# Lesson_06.net
KiCad netlist of a schematic drawn in Altium Designer
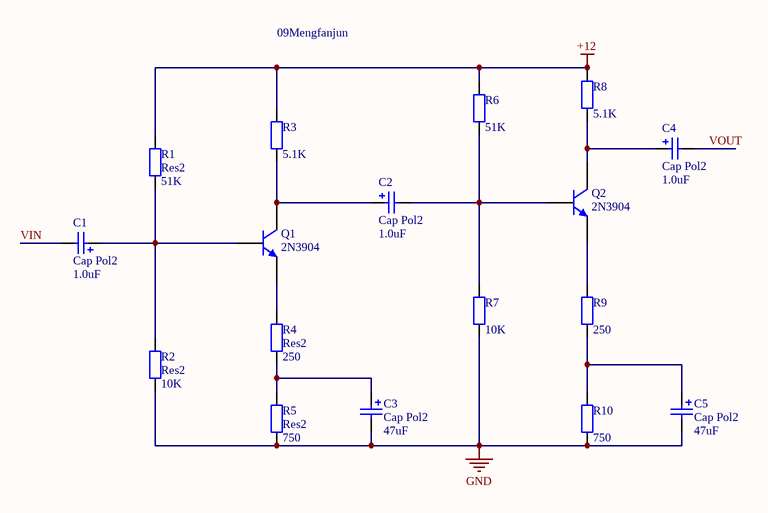
[diagram p0: Lesson_06.SchDoc]

(export (version "E")
  (design (tool "Eeschema 10.0.6"))
  (components
    (comp (ref "C1")
      (value "Cap Pol2")
      (footprint "POLAR0.8")
      (description "Polarized Capacitor (Axial)")
      (fields (field (name "ALTIUM_VALUE") "1.0uF") (field (name "PUBLISHER") "Altium Limited"))
      (libsource (lib "Miscellaneous Devices") (part "Cap Pol2"))
    )
    (comp (ref "C2")
      (value "Cap Pol2")
      (footprint "POLAR0.8")
      (description "Polarized Capacitor (Axial)")
      (fields (field (name "ALTIUM_VALUE") "1.0uF") (field (name "PUBLISHER") "Altium Limited"))
      (libsource (lib "Miscellaneous Devices") (part "Cap Pol2"))
    )
    (comp (ref "C3")
      (value "Cap Pol2")
      (footprint "POLAR0.8")
      (description "Polarized Capacitor (Axial)")
      (fields (field (name "ALTIUM_VALUE") "47uF") (field (name "PUBLISHER") "Altium Limited"))
      (libsource (lib "Miscellaneous Devices") (part "Cap Pol2"))
    )
    (comp (ref "C4")
      (value "Cap Pol2")
      (footprint "POLAR0.8")
      (description "Polarized Capacitor (Axial)")
      (fields (field (name "ALTIUM_VALUE") "1.0uF") (field (name "PUBLISHER") "Altium Limited"))
      (libsource (lib "Miscellaneous Devices") (part "Cap Pol2"))
    )
    (comp (ref "C5")
      (value "Cap Pol2")
      (footprint "POLAR0.8")
      (description "Polarized Capacitor (Axial)")
      (fields (field (name "ALTIUM_VALUE") "47uF") (field (name "PUBLISHER") "Altium Limited"))
      (libsource (lib "Miscellaneous Devices") (part "Cap Pol2"))
    )
    (comp (ref "Q1")
      (value "2N3904")
      (footprint "TO-92A")
      (description "NPN General Purpose Amplifier")
      (fields (field (name "PUBLISHER") "Altium Limited"))
      (libsource (lib "Miscellaneous Devices") (part "2N3904"))
    )
    (comp (ref "Q2")
      (value "2N3904")
      (footprint "TO-92A")
      (description "NPN General Purpose Amplifier")
      (fields (field (name "PUBLISHER") "Altium Limited"))
      (libsource (lib "Miscellaneous Devices") (part "2N3904"))
    )
    (comp (ref "R1")
      (value "Res2")
      (footprint "AXIAL-0.4")
      (description "Resistor")
      (fields (field (name "ALTIUM_VALUE") "51K") (field (name "PUBLISHER") "Altium Limited"))
      (libsource (lib "Miscellaneous Devices") (part "Res2"))
    )
    (comp (ref "R2")
      (value "Res2")
      (footprint "AXIAL-0.4")
      (description "Resistor")
      (fields (field (name "ALTIUM_VALUE") "10K") (field (name "PUBLISHER") "Altium Limited"))
      (libsource (lib "Miscellaneous Devices") (part "Res2"))
    )
    (comp (ref "R3")
      (value "5.1K")
      (footprint "AXIAL-0.4")
      (description "Resistor")
      (fields (field (name "Comment") "Res2") (field (name "PUBLISHER") "Altium Limited"))
      (libsource (lib "Miscellaneous Devices") (part "Res2"))
    )
    (comp (ref "R4")
      (value "Res2")
      (footprint "AXIAL-0.4")
      (description "Resistor")
      (fields (field (name "ALTIUM_VALUE") "250") (field (name "PUBLISHER") "Altium Limited"))
      (libsource (lib "Miscellaneous Devices") (part "Res2"))
    )
    (comp (ref "R5")
      (value "Res2")
      (footprint "AXIAL-0.4")
      (description "Resistor")
      (fields (field (name "ALTIUM_VALUE") "750") (field (name "PUBLISHER") "Altium Limited"))
      (libsource (lib "Miscellaneous Devices") (part "Res2"))
    )
    (comp (ref "R6")
      (value "51K")
      (footprint "AXIAL-0.4")
      (description "Resistor")
      (fields (field (name "Comment") "Res2") (field (name "PUBLISHER") "Altium Limited"))
      (libsource (lib "Miscellaneous Devices") (part "Res2"))
    )
    (comp (ref "R7")
      (value "10K")
      (footprint "AXIAL-0.4")
      (description "Resistor")
      (fields (field (name "PUBLISHER") "Altium Limited"))
      (libsource (lib "Miscellaneous Devices") (part "Res2"))
    )
    (comp (ref "R8")
      (value "5.1K")
      (footprint "AXIAL-0.4")
      (description "Resistor")
      (fields (field (name "Comment") "Res2") (field (name "PUBLISHER") "Altium Limited"))
      (libsource (lib "Miscellaneous Devices") (part "Res2"))
    )
    (comp (ref "R9")
      (value "250")
      (footprint "AXIAL-0.4")
      (description "Resistor")
      (fields (field (name "Comment") "Res2") (field (name "PUBLISHER") "Altium Limited"))
      (libsource (lib "Miscellaneous Devices") (part "Res2"))
    )
    (comp (ref "R10")
      (value "750")
      (footprint "AXIAL-0.4")
      (description "Resistor")
      (fields (field (name "Comment") "Res2") (field (name "PUBLISHER") "Altium Limited"))
      (libsource (lib "Miscellaneous Devices") (part "Res2"))
    )
  )
  (nets
    (net (code "1") (name "+12") (class "Default")
      (node (ref "R1") (pin "2") (pinfunction "2_2") (pintype "passive"))
      (node (ref "R3") (pin "2") (pinfunction "2_2") (pintype "passive"))
      (node (ref "R6") (pin "2") (pinfunction "2_2") (pintype "passive"))
      (node (ref "R8") (pin "2") (pinfunction "2_2") (pintype "passive"))
    )
    (net (code "2") (name "/VIN") (class "Default")
      (node (ref "C1") (pin "2") (pinfunction "2_2") (pintype "passive"))
    )
    (net (code "3") (name "/VOUT") (class "Default")
      (node (ref "C4") (pin "2") (pinfunction "2_2") (pintype "passive"))
    )
    (net (code "4") (name "GND") (class "Default")
      (node (ref "C3") (pin "2") (pinfunction "2_2") (pintype "passive"))
      (node (ref "C5") (pin "2") (pinfunction "2_2") (pintype "passive"))
      (node (ref "R10") (pin "1") (pinfunction "1_1") (pintype "passive"))
      (node (ref "R2") (pin "1") (pinfunction "1_1") (pintype "passive"))
      (node (ref "R5") (pin "1") (pinfunction "1_1") (pintype "passive"))
      (node (ref "R7") (pin "1") (pinfunction "1_1") (pintype "passive"))
    )
    (net (code "5") (name "Net-(C3-Pad1)") (class "Default")
      (node (ref "C3") (pin "1") (pinfunction "1_1") (pintype "passive"))
      (node (ref "R4") (pin "1") (pinfunction "1_1") (pintype "passive"))
      (node (ref "R5") (pin "2") (pinfunction "2_2") (pintype "passive"))
    )
    (net (code "6") (name "Net-(C5-Pad1)") (class "Default")
      (node (ref "C5") (pin "1") (pinfunction "1_1") (pintype "passive"))
      (node (ref "R10") (pin "2") (pinfunction "2_2") (pintype "passive"))
      (node (ref "R9") (pin "1") (pinfunction "1_1") (pintype "passive"))
    )
    (net (code "7") (name "Net-(Q1-B)") (class "Default")
      (node (ref "C1") (pin "1") (pinfunction "1_1") (pintype "passive"))
      (node (ref "Q1") (pin "2") (pinfunction "B_2") (pintype "passive"))
      (node (ref "R1") (pin "1") (pinfunction "1_1") (pintype "passive"))
      (node (ref "R2") (pin "2") (pinfunction "2_2") (pintype "passive"))
    )
    (net (code "8") (name "Net-(Q1-C)") (class "Default")
      (node (ref "C2") (pin "1") (pinfunction "1_1") (pintype "passive"))
      (node (ref "Q1") (pin "3") (pinfunction "C_3") (pintype "passive"))
      (node (ref "R3") (pin "1") (pinfunction "1_1") (pintype "passive"))
    )
    (net (code "9") (name "Net-(Q1-E)") (class "Default")
      (node (ref "Q1") (pin "1") (pinfunction "E_1") (pintype "passive"))
      (node (ref "R4") (pin "2") (pinfunction "2_2") (pintype "passive"))
    )
    (net (code "10") (name "Net-(Q2-B)") (class "Default")
      (node (ref "C2") (pin "2") (pinfunction "2_2") (pintype "passive"))
      (node (ref "Q2") (pin "2") (pinfunction "B_2") (pintype "passive"))
      (node (ref "R6") (pin "1") (pinfunction "1_1") (pintype "passive"))
      (node (ref "R7") (pin "2") (pinfunction "2_2") (pintype "passive"))
    )
    (net (code "11") (name "Net-(Q2-C)") (class "Default")
      (node (ref "C4") (pin "1") (pinfunction "1_1") (pintype "passive"))
      (node (ref "Q2") (pin "3") (pinfunction "C_3") (pintype "passive"))
      (node (ref "R8") (pin "1") (pinfunction "1_1") (pintype "passive"))
    )
    (net (code "12") (name "Net-(Q2-E)") (class "Default")
      (node (ref "Q2") (pin "1") (pinfunction "E_1") (pintype "passive"))
      (node (ref "R9") (pin "2") (pinfunction "2_2") (pintype "passive"))
    )
  )
)
